# levelshift6x.net
KiCad netlist of a schematic drawn in Altium Designer
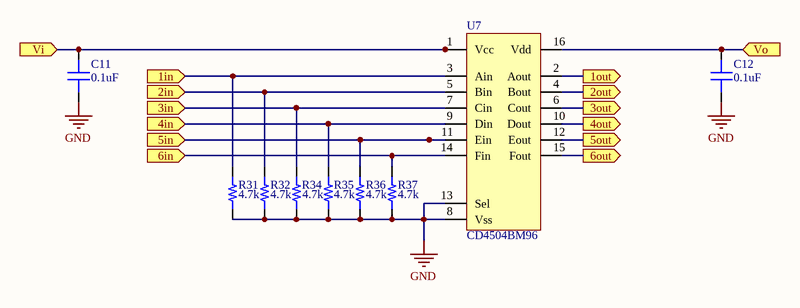
[diagram p0: levelshift6x.SchDoc]

(export (version "E")
  (design (tool "Eeschema 10.0.6"))
  (components
    (comp (ref "C11")
      (value "capacitor")
      (footprint "0603")
      (description "Generic 0603 capacitor")
      (fields (field (name "CAPACITANCE") "0.1uF"))
      (libsource (lib "altlib") (part "capacitor"))
    )
    (comp (ref "C12")
      (value "capacitor")
      (footprint "0603")
      (description "Generic 0603 capacitor")
      (fields (field (name "CAPACITANCE") "0.1uF"))
      (libsource (lib "altlib") (part "capacitor"))
    )
    (comp (ref "R31")
      (value "resistor")
      (footprint "0603")
      (fields (field (name "RESISTANCE") "4.7k"))
      (libsource (lib "altlib") (part "resistor"))
    )
    (comp (ref "R32")
      (value "resistor")
      (footprint "0603")
      (fields (field (name "RESISTANCE") "4.7k"))
      (libsource (lib "altlib") (part "resistor"))
    )
    (comp (ref "R34")
      (value "resistor")
      (footprint "0603")
      (fields (field (name "RESISTANCE") "4.7k"))
      (libsource (lib "altlib") (part "resistor"))
    )
    (comp (ref "R35")
      (value "resistor")
      (footprint "0603")
      (fields (field (name "RESISTANCE") "4.7k"))
      (libsource (lib "altlib") (part "resistor"))
    )
    (comp (ref "R36")
      (value "resistor")
      (footprint "0603")
      (fields (field (name "RESISTANCE") "4.7k"))
      (libsource (lib "altlib") (part "resistor"))
    )
    (comp (ref "R37")
      (value "resistor")
      (footprint "0603")
      (fields (field (name "RESISTANCE") "4.7k"))
      (libsource (lib "altlib") (part "resistor"))
    )
    (comp (ref "U7")
      (value "CD4504BM96")
      (footprint "SOIC-16")
      (description "Voltage Level Translator Unidirectional 1 Cir")
      (libsource (lib "altlib") (part "CD4504BM96"))
    )
  )
  (nets
    (net (code "1") (name "/1in") (class "Default")
      (node (ref "R31") (pin "2") (pinfunction "2_2") (pintype "passive"))
      (node (ref "U7") (pin "3") (pinfunction "Ain_3") (pintype "passive"))
    )
    (net (code "2") (name "/1out") (class "Default")
      (node (ref "U7") (pin "2") (pinfunction "Aout_2") (pintype "passive"))
    )
    (net (code "3") (name "/2in") (class "Default")
      (node (ref "R32") (pin "2") (pinfunction "2_2") (pintype "passive"))
      (node (ref "U7") (pin "5") (pinfunction "Bin_5") (pintype "passive"))
    )
    (net (code "4") (name "/2out") (class "Default")
      (node (ref "U7") (pin "4") (pinfunction "Bout_4") (pintype "passive"))
    )
    (net (code "5") (name "/3in") (class "Default")
      (node (ref "R34") (pin "2") (pinfunction "2_2") (pintype "passive"))
      (node (ref "U7") (pin "7") (pinfunction "Cin_7") (pintype "passive"))
    )
    (net (code "6") (name "/3out") (class "Default")
      (node (ref "U7") (pin "6") (pinfunction "Cout_6") (pintype "passive"))
    )
    (net (code "7") (name "/4in") (class "Default")
      (node (ref "R35") (pin "2") (pinfunction "2_2") (pintype "passive"))
      (node (ref "U7") (pin "9") (pinfunction "Din_9") (pintype "passive"))
    )
    (net (code "8") (name "/4out") (class "Default")
      (node (ref "U7") (pin "10") (pinfunction "Dout_10") (pintype "passive"))
    )
    (net (code "9") (name "/5in") (class "Default")
      (node (ref "R36") (pin "2") (pinfunction "2_2") (pintype "passive"))
      (node (ref "U7") (pin "11") (pinfunction "Ein_11") (pintype "passive"))
    )
    (net (code "10") (name "/5out") (class "Default")
      (node (ref "U7") (pin "12") (pinfunction "Eout_12") (pintype "passive"))
    )
    (net (code "11") (name "/6in") (class "Default")
      (node (ref "R37") (pin "2") (pinfunction "2_2") (pintype "passive"))
      (node (ref "U7") (pin "14") (pinfunction "Fin_14") (pintype "passive"))
    )
    (net (code "12") (name "/6out") (class "Default")
      (node (ref "U7") (pin "15") (pinfunction "Fout_15") (pintype "passive"))
    )
    (net (code "13") (name "/Vi") (class "Default")
      (node (ref "C11") (pin "2") (pinfunction "2_2") (pintype "passive"))
      (node (ref "U7") (pin "1") (pinfunction "Vcc_1") (pintype "passive"))
    )
    (net (code "14") (name "/Vo") (class "Default")
      (node (ref "C12") (pin "2") (pinfunction "2_2") (pintype "passive"))
      (node (ref "U7") (pin "16") (pinfunction "Vdd_16") (pintype "passive"))
    )
    (net (code "15") (name "GND") (class "Default")
      (node (ref "C11") (pin "1") (pinfunction "1_1") (pintype "passive"))
      (node (ref "C12") (pin "1") (pinfunction "1_1") (pintype "passive"))
      (node (ref "R31") (pin "1") (pinfunction "1_1") (pintype "passive"))
      (node (ref "R32") (pin "1") (pinfunction "1_1") (pintype "passive"))
      (node (ref "R34") (pin "1") (pinfunction "1_1") (pintype "passive"))
      (node (ref "R35") (pin "1") (pinfunction "1_1") (pintype "passive"))
      (node (ref "R36") (pin "1") (pinfunction "1_1") (pintype "passive"))
      (node (ref "R37") (pin "1") (pinfunction "1_1") (pintype "passive"))
      (node (ref "U7") (pin "13") (pinfunction "Sel_13") (pintype "passive"))
      (node (ref "U7") (pin "8") (pinfunction "Vss_8") (pintype "passive"))
    )
  )
)
